# ChairControlMini.net
KiCad netlist of a schematic drawn in EAGLE
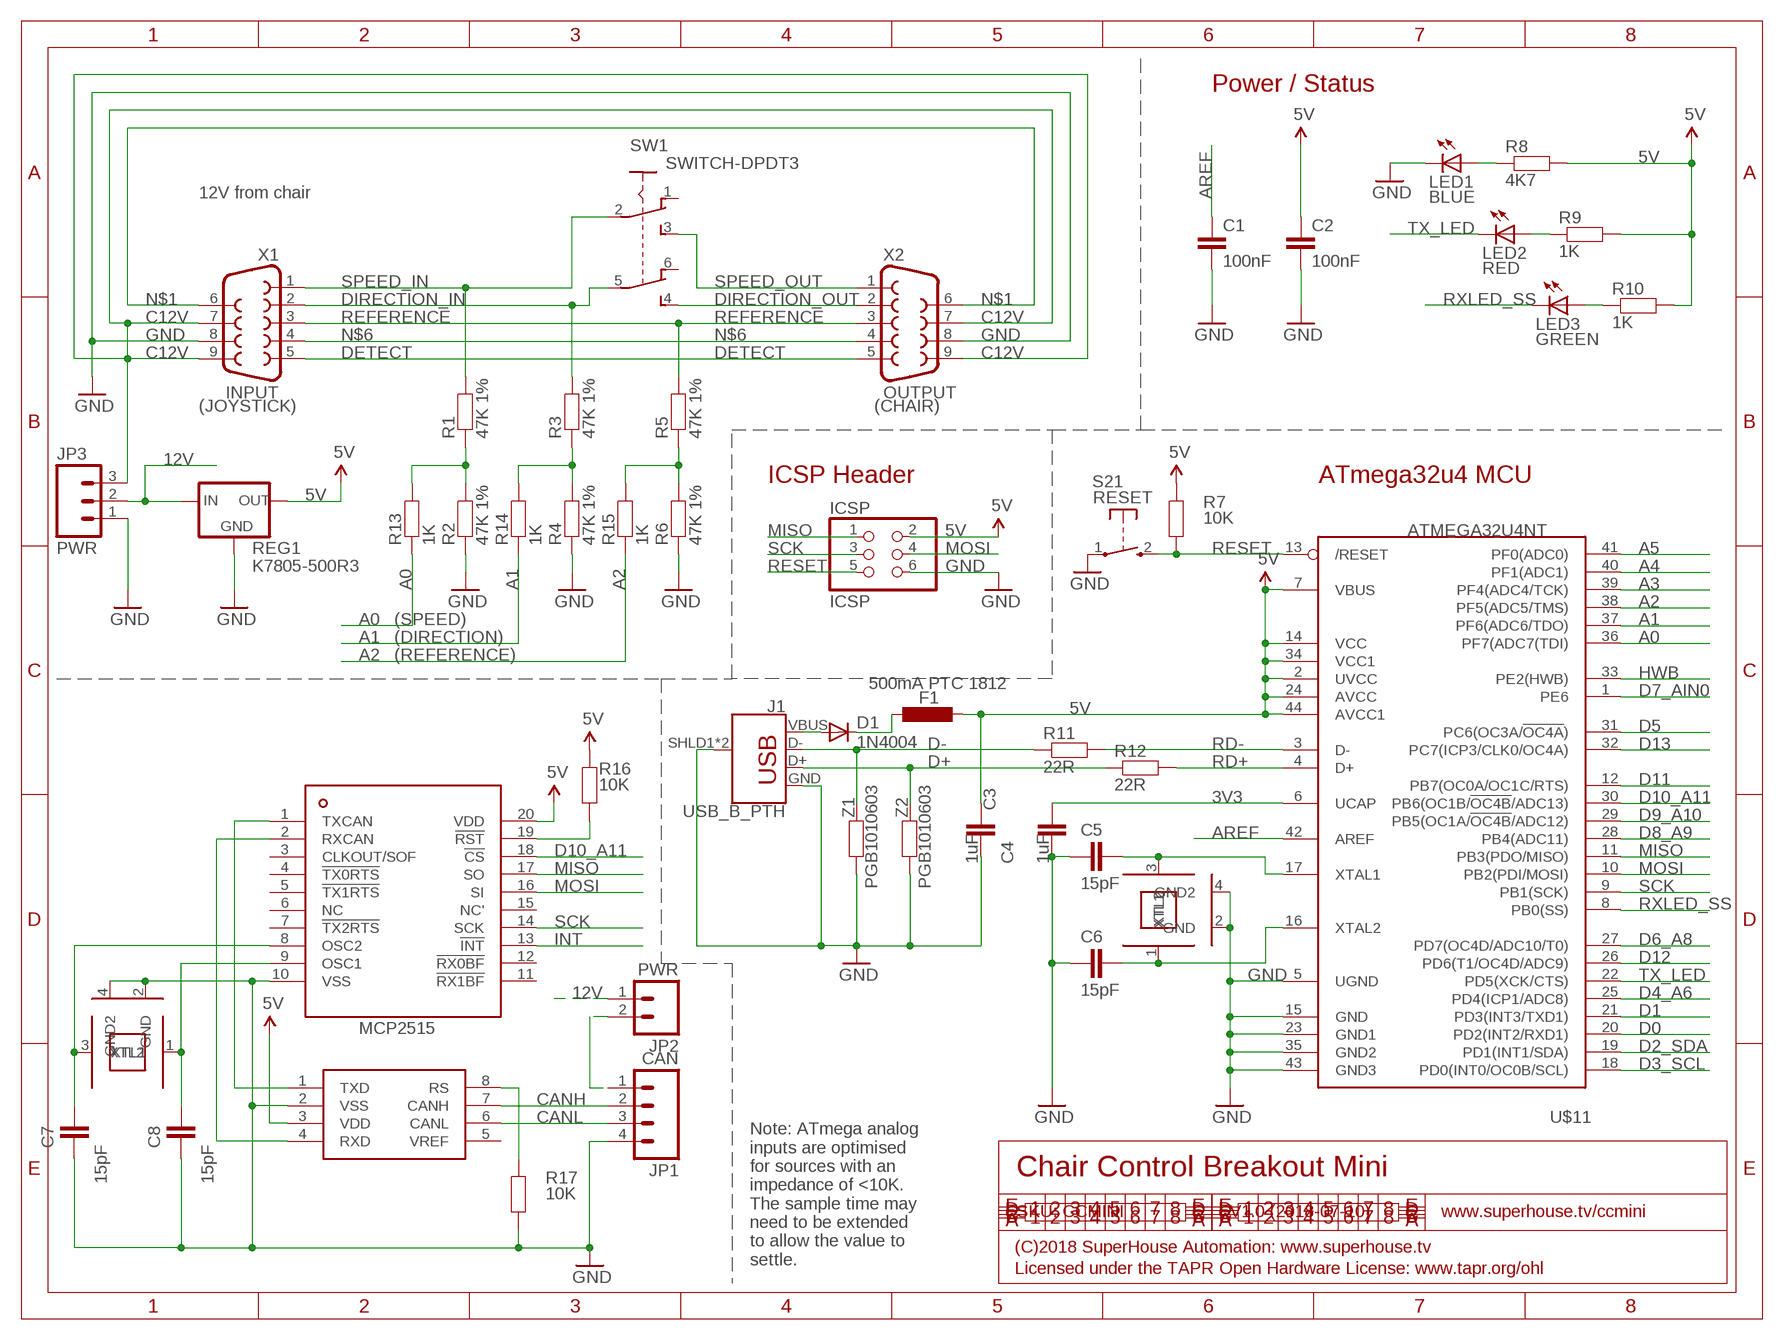
[diagram p0: schematic, sheet 1]

(export (version "E")
  (design (tool "Eeschema 10.0.6"))
  (components
    (comp (ref "C1")
      (value "100nF")
      (footprint "eagle-import:0603")
      (libsource (lib "eagle-import") (part "CAP0603"))
    )
    (comp (ref "C2")
      (value "100nF")
      (footprint "eagle-import:0603")
      (libsource (lib "eagle-import") (part "CAP0603"))
    )
    (comp (ref "C3")
      (value "1uF")
      (footprint "eagle-import:0603")
      (libsource (lib "eagle-import") (part "CAP0603"))
    )
    (comp (ref "C4")
      (value "1uF")
      (footprint "eagle-import:0603")
      (libsource (lib "eagle-import") (part "CAP0603"))
    )
    (comp (ref "C5")
      (value "15pF")
      (footprint "eagle-import:0603")
      (libsource (lib "eagle-import") (part "CAP0603"))
    )
    (comp (ref "C6")
      (value "15pF")
      (footprint "eagle-import:0603")
      (libsource (lib "eagle-import") (part "CAP0603"))
    )
    (comp (ref "C7")
      (value "15pF")
      (footprint "eagle-import:0603")
      (libsource (lib "eagle-import") (part "CAP0603"))
    )
    (comp (ref "C8")
      (value "15pF")
      (footprint "eagle-import:0603")
      (libsource (lib "eagle-import") (part "CAP0603"))
    )
    (comp (ref "D1")
      (value "1N4004")
      (footprint "eagle-import:SMB-DIODE")
      (libsource (lib "eagle-import") (part "DIODESMB"))
    )
    (comp (ref "F1")
      (value "500mA PTC 1812")
      (footprint "eagle-import:L1812")
      (libsource (lib "eagle-import") (part "L-EUL1812"))
    )
    (comp (ref "ICSP")
      (value "ICSP")
      (footprint "eagle-import:2X03")
      (libsource (lib "eagle-import") (part "PINHD-2X3"))
    )
    (comp (ref "J1")
      (value "USB_B_PTH")
      (footprint "eagle-import:USB-B-PTH")
      (libsource (lib "eagle-import") (part "USB_B_PTH"))
    )
    (comp (ref "JP1")
      (value "CAN")
      (footprint "eagle-import:1X04")
      (libsource (lib "eagle-import") (part "M04PTH"))
    )
    (comp (ref "JP2")
      (value "PWR")
      (footprint "eagle-import:1X02")
      (libsource (lib "eagle-import") (part "M02PTH"))
    )
    (comp (ref "JP3")
      (value "PWR")
      (footprint "eagle-import:1X03")
      (libsource (lib "eagle-import") (part "M03PTH"))
    )
    (comp (ref "LED1")
      (value "BLUE")
      (footprint "eagle-import:LED-0603")
      (libsource (lib "eagle-import") (part "LED0603"))
    )
    (comp (ref "LED2")
      (value "RED")
      (footprint "eagle-import:LED-0603")
      (libsource (lib "eagle-import") (part "LED0603"))
    )
    (comp (ref "LED3")
      (value "GREEN")
      (footprint "eagle-import:LED-0603")
      (libsource (lib "eagle-import") (part "LED0603"))
    )
    (comp (ref "R1")
      (value "47K 1%")
      (footprint "eagle-import:0603")
      (libsource (lib "eagle-import") (part "RESISTOR0603"))
    )
    (comp (ref "R2")
      (value "47K 1%")
      (footprint "eagle-import:0603")
      (libsource (lib "eagle-import") (part "RESISTOR0603"))
    )
    (comp (ref "R3")
      (value "47K 1%")
      (footprint "eagle-import:0603")
      (libsource (lib "eagle-import") (part "RESISTOR0603"))
    )
    (comp (ref "R4")
      (value "47K 1%")
      (footprint "eagle-import:0603")
      (libsource (lib "eagle-import") (part "RESISTOR0603"))
    )
    (comp (ref "R5")
      (value "47K 1%")
      (footprint "eagle-import:0603")
      (libsource (lib "eagle-import") (part "RESISTOR0603"))
    )
    (comp (ref "R6")
      (value "47K 1%")
      (footprint "eagle-import:0603")
      (libsource (lib "eagle-import") (part "RESISTOR0603"))
    )
    (comp (ref "R7")
      (value "10K")
      (footprint "eagle-import:0603")
      (libsource (lib "eagle-import") (part "freetronics-master-v1.1_RESISTOR0603"))
    )
    (comp (ref "R8")
      (value "4K7")
      (footprint "eagle-import:0603")
      (libsource (lib "eagle-import") (part "RESISTOR0603"))
    )
    (comp (ref "R9")
      (value "1K")
      (footprint "eagle-import:0603")
      (libsource (lib "eagle-import") (part "RESISTOR0603"))
    )
    (comp (ref "R10")
      (value "1K")
      (footprint "eagle-import:0603")
      (libsource (lib "eagle-import") (part "RESISTOR0603"))
    )
    (comp (ref "R11")
      (value "22R")
      (footprint "eagle-import:0603")
      (libsource (lib "eagle-import") (part "RESISTOR0603"))
    )
    (comp (ref "R12")
      (value "22R")
      (footprint "eagle-import:0603")
      (libsource (lib "eagle-import") (part "RESISTOR0603"))
    )
    (comp (ref "R13")
      (value "1K")
      (footprint "eagle-import:0603")
      (libsource (lib "eagle-import") (part "RESISTOR0603"))
    )
    (comp (ref "R14")
      (value "1K")
      (footprint "eagle-import:0603")
      (libsource (lib "eagle-import") (part "RESISTOR0603"))
    )
    (comp (ref "R15")
      (value "1K")
      (footprint "eagle-import:0603")
      (libsource (lib "eagle-import") (part "RESISTOR0603"))
    )
    (comp (ref "R16")
      (value "10K")
      (footprint "eagle-import:0603")
      (libsource (lib "eagle-import") (part "freetronics-master-v1.1_RESISTOR0603"))
    )
    (comp (ref "R17")
      (value "10K")
      (footprint "eagle-import:0603")
      (libsource (lib "eagle-import") (part "freetronics-master-v1.1_RESISTOR0603"))
    )
    (comp (ref "REG1")
      (value "K7805-500R3")
      (footprint "eagle-import:K78XX-500R3")
      (libsource (lib "eagle-import") (part "K78XX-500R3"))
    )
    (comp (ref "S21")
      (value "RESET")
      (footprint "eagle-import:TACTILE_SWITCH_SMD_2PIN_TINY")
      (libsource (lib "eagle-import") (part "TAC_SWITCH_2PINSMT"))
    )
    (comp (ref "SW1")
      (value "SWITCH-DPDT3")
      (footprint "eagle-import:7201SD9AV2BE")
      (libsource (lib "eagle-import") (part "SWITCH-DPDT3"))
    )
    (comp (ref "U$4")
      (value "MCP2515")
      (footprint "eagle-import:TSSOP20")
      (libsource (lib "eagle-import") (part "MCP2515"))
    )
    (comp (ref "U$11")
      (value "ATMEGA32U4NT")
      (footprint "eagle-import:TQFP44")
      (libsource (lib "eagle-import") (part "ATMEGA32U4NT"))
    )
    (comp (ref "U1")
      (value "MCP2551")
      (footprint "eagle-import:SO08")
      (libsource (lib "eagle-import") (part "MCP2551"))
    )
    (comp (ref "X1")
      (value "INPUT")
      (footprint "eagle-import:DB9_MALE")
      (libsource (lib "eagle-import") (part "DB9MALE"))
    )
    (comp (ref "X2")
      (value "OUTPUT")
      (footprint "eagle-import:DB9")
      (libsource (lib "eagle-import") (part "DB9FEMALE"))
    )
    (comp (ref "XTL1")
      (value "16MHz")
      (footprint "eagle-import:CRYSTAL-SMD-3X2")
      (libsource (lib "eagle-import") (part "CRYSTAL-GND3X2"))
    )
    (comp (ref "XTL2")
      (value "8MHz")
      (footprint "eagle-import:CRYSTAL-SMD-3X2")
      (libsource (lib "eagle-import") (part "CRYSTAL-GND3X2"))
    )
    (comp (ref "Z1")
      (value "PGB1010603")
      (footprint "eagle-import:0603")
      (libsource (lib "eagle-import") (part "freetronics-master-v1.1_RESISTOR0603"))
    )
    (comp (ref "Z2")
      (value "PGB1010603")
      (footprint "eagle-import:0603")
      (libsource (lib "eagle-import") (part "freetronics-master-v1.1_RESISTOR0603"))
    )
  )
  (nets
    (net (code "1") (name "/3V3") (class "Default")
      (node (ref "C4") (pin "2") (pinfunction "2_2") (pintype "passive"))
      (node (ref "U$11") (pin "6") (pinfunction "UCAP_6") (pintype "bidirectional"))
    )
    (net (code "2") (name "/12V") (class "Default")
      (node (ref "JP2") (pin "1") (pinfunction "1_1") (pintype "passive"))
      (node (ref "JP3") (pin "2") (pinfunction "2_2") (pintype "passive"))
      (node (ref "REG1") (pin "1") (pinfunction "IN_1") (pintype "input"))
    )
    (net (code "3") (name "/A0") (class "Default")
      (node (ref "R13") (pin "1") (pinfunction "1_1") (pintype "passive"))
      (node (ref "U$11") (pin "36") (pinfunction "PF7(ADC7(TDI)_36") (pintype "bidirectional"))
    )
    (net (code "4") (name "/A1") (class "Default")
      (node (ref "R14") (pin "1") (pinfunction "1_1") (pintype "passive"))
      (node (ref "U$11") (pin "37") (pinfunction "PF6(ADC6/TDO)_37") (pintype "bidirectional"))
    )
    (net (code "5") (name "/A2") (class "Default")
      (node (ref "R15") (pin "1") (pinfunction "1_1") (pintype "passive"))
      (node (ref "U$11") (pin "38") (pinfunction "PF5(ADC5/TMS)_38") (pintype "bidirectional"))
    )
    (net (code "6") (name "/A3") (class "Default")
      (node (ref "U$11") (pin "39") (pinfunction "PF4(ADC4/TCK)_39") (pintype "bidirectional"))
    )
    (net (code "7") (name "/A4") (class "Default")
      (node (ref "U$11") (pin "40") (pinfunction "PF1(ADC1)_40") (pintype "bidirectional"))
    )
    (net (code "8") (name "/A5") (class "Default")
      (node (ref "U$11") (pin "41") (pinfunction "PF0(ADC0)_41") (pintype "bidirectional"))
    )
    (net (code "9") (name "/AREF") (class "Default")
      (node (ref "C1") (pin "1") (pinfunction "1_1") (pintype "passive"))
      (node (ref "U$11") (pin "42") (pinfunction "AREF_42") (pintype "bidirectional"))
    )
    (net (code "10") (name "/C12V") (class "Default")
      (node (ref "JP3") (pin "3") (pinfunction "3_3") (pintype "passive"))
      (node (ref "X1") (pin "7") (pinfunction "7_7") (pintype "passive"))
      (node (ref "X1") (pin "9") (pinfunction "9_9") (pintype "passive"))
      (node (ref "X2") (pin "7") (pinfunction "7_7") (pintype "passive"))
      (node (ref "X2") (pin "9") (pinfunction "9_9") (pintype "passive"))
    )
    (net (code "11") (name "/CANH") (class "Default")
      (node (ref "JP1") (pin "2") (pinfunction "2_2") (pintype "passive"))
      (node (ref "U1") (pin "7") (pinfunction "CANH_7") (pintype "bidirectional"))
    )
    (net (code "12") (name "/CANL") (class "Default")
      (node (ref "JP1") (pin "3") (pinfunction "3_3") (pintype "passive"))
      (node (ref "U1") (pin "6") (pinfunction "CANL_6") (pintype "bidirectional"))
    )
    (net (code "13") (name "/D+") (class "Default")
      (node (ref "J1") (pin "D+") (pinfunction "D+_D+") (pintype "bidirectional"))
      (node (ref "R12") (pin "1") (pinfunction "1_1") (pintype "passive"))
      (node (ref "Z2") (pin "2") (pinfunction "2_2") (pintype "passive"))
    )
    (net (code "14") (name "/D-") (class "Default")
      (node (ref "J1") (pin "D-") (pinfunction "D-_D-") (pintype "bidirectional"))
      (node (ref "R11") (pin "1") (pinfunction "1_1") (pintype "passive"))
      (node (ref "Z1") (pin "2") (pinfunction "2_2") (pintype "passive"))
    )
    (net (code "15") (name "/D0") (class "Default")
      (node (ref "U$11") (pin "20") (pinfunction "PD2(INT2/RXD1)_20") (pintype "bidirectional"))
    )
    (net (code "16") (name "/D1") (class "Default")
      (node (ref "U$11") (pin "21") (pinfunction "PD3(INT3/TXD1)_21") (pintype "bidirectional"))
    )
    (net (code "17") (name "/D2_SDA") (class "Default")
      (node (ref "U$11") (pin "19") (pinfunction "PD1(INT1/SDA)_19") (pintype "bidirectional"))
    )
    (net (code "18") (name "/D3_SCL") (class "Default")
      (node (ref "U$11") (pin "18") (pinfunction "PD0(INT0/OC0B/SCL)_18") (pintype "bidirectional"))
    )
    (net (code "19") (name "/D4_A6") (class "Default")
      (node (ref "U$11") (pin "25") (pinfunction "PD4(ICP1/ADC8)_25") (pintype "bidirectional"))
    )
    (net (code "20") (name "/D5") (class "Default")
      (node (ref "U$11") (pin "31") (pinfunction "PC6(OC3A/~{OC4A})_31") (pintype "bidirectional"))
    )
    (net (code "21") (name "/D6_A8") (class "Default")
      (node (ref "U$11") (pin "27") (pinfunction "PD7(OC4D/ADC10/T0)_27") (pintype "bidirectional"))
    )
    (net (code "22") (name "/D7_AIN0") (class "Default")
      (node (ref "U$11") (pin "1") (pinfunction "PE6_1") (pintype "bidirectional"))
    )
    (net (code "23") (name "/D8_A9") (class "Default")
      (node (ref "U$11") (pin "28") (pinfunction "PB4(ADC11)_28") (pintype "bidirectional"))
    )
    (net (code "24") (name "/D9_A10") (class "Default")
      (node (ref "U$11") (pin "29") (pinfunction "PB5(OC1A/~{OC4B}/ADC12)_29") (pintype "bidirectional"))
    )
    (net (code "25") (name "/D10_A11") (class "Default")
      (node (ref "U$11") (pin "30") (pinfunction "PB6(OC1B/~{OC4B}/ADC13)_30") (pintype "bidirectional"))
      (node (ref "U$4") (pin "18") (pinfunction "~{CS}_18") (pintype "bidirectional"))
    )
    (net (code "26") (name "/D11") (class "Default")
      (node (ref "U$11") (pin "12") (pinfunction "PB7(OC0A/OC1C/RTS)_12") (pintype "bidirectional"))
    )
    (net (code "27") (name "/D12") (class "Default")
      (node (ref "U$11") (pin "26") (pinfunction "PD6(T1/OC4D/ADC9)_26") (pintype "bidirectional"))
    )
    (net (code "28") (name "/D13") (class "Default")
      (node (ref "U$11") (pin "32") (pinfunction "PC7(ICP3/CLK0/OC4A)_32") (pintype "bidirectional"))
    )
    (net (code "29") (name "/DETECT") (class "Default")
      (node (ref "X1") (pin "5") (pinfunction "5_5") (pintype "passive"))
      (node (ref "X2") (pin "5") (pinfunction "5_5") (pintype "passive"))
    )
    (net (code "30") (name "/DIRECTION_IN") (class "Default")
      (node (ref "R3") (pin "2") (pinfunction "2_2") (pintype "passive"))
      (node (ref "SW1") (pin "5") (pinfunction "5_5") (pintype "passive"))
      (node (ref "X1") (pin "2") (pinfunction "2_2") (pintype "passive"))
    )
    (net (code "31") (name "/DIRECTION_OUT") (class "Default")
      (node (ref "SW1") (pin "4") (pinfunction "4_4") (pintype "passive"))
      (node (ref "X2") (pin "2") (pinfunction "2_2") (pintype "passive"))
    )
    (net (code "32") (name "/HWB") (class "Default")
      (node (ref "U$11") (pin "33") (pinfunction "PE2(HWB)_33") (pintype "bidirectional"))
    )
    (net (code "33") (name "/INT") (class "Default")
      (node (ref "U$4") (pin "13") (pinfunction "~{INT}_13") (pintype "bidirectional"))
    )
    (net (code "34") (name "/MISO") (class "Default")
      (node (ref "ICSP") (pin "1") (pinfunction "1_1") (pintype "passive"))
      (node (ref "U$11") (pin "11") (pinfunction "PB3(PDO/MISO)_11") (pintype "bidirectional"))
      (node (ref "U$4") (pin "17") (pinfunction "SO_17") (pintype "bidirectional"))
    )
    (net (code "35") (name "/MOSI") (class "Default")
      (node (ref "ICSP") (pin "4") (pinfunction "4_4") (pintype "passive"))
      (node (ref "U$11") (pin "10") (pinfunction "PB2(PDI/MOSI)_10") (pintype "bidirectional"))
      (node (ref "U$4") (pin "16") (pinfunction "SI_16") (pintype "bidirectional"))
    )
    (net (code "36") (name "/N$1") (class "Default")
      (node (ref "X1") (pin "6") (pinfunction "6_6") (pintype "passive"))
      (node (ref "X2") (pin "6") (pinfunction "6_6") (pintype "passive"))
    )
    (net (code "37") (name "/N$6") (class "Default")
      (node (ref "X1") (pin "4") (pinfunction "4_4") (pintype "passive"))
      (node (ref "X2") (pin "4") (pinfunction "4_4") (pintype "passive"))
    )
    (net (code "38") (name "/RD+") (class "Default")
      (node (ref "R12") (pin "2") (pinfunction "2_2") (pintype "passive"))
      (node (ref "U$11") (pin "4") (pinfunction "D+_4") (pintype "bidirectional"))
    )
    (net (code "39") (name "/RD-") (class "Default")
      (node (ref "R11") (pin "2") (pinfunction "2_2") (pintype "passive"))
      (node (ref "U$11") (pin "3") (pinfunction "D-_3") (pintype "bidirectional"))
    )
    (net (code "40") (name "/REFERENCE") (class "Default")
      (node (ref "R5") (pin "2") (pinfunction "2_2") (pintype "passive"))
      (node (ref "X1") (pin "3") (pinfunction "3_3") (pintype "passive"))
      (node (ref "X2") (pin "3") (pinfunction "3_3") (pintype "passive"))
    )
    (net (code "41") (name "/RESET") (class "Default")
      (node (ref "ICSP") (pin "5") (pinfunction "5_5") (pintype "passive"))
      (node (ref "R7") (pin "1") (pinfunction "1_1") (pintype "passive"))
      (node (ref "S21") (pin "2") (pinfunction "S_2") (pintype "passive"))
      (node (ref "U$11") (pin "13") (pinfunction "/RESET_13") (pintype "bidirectional"))
    )
    (net (code "42") (name "/RXLED_SS") (class "Default")
      (node (ref "LED3") (pin "C") (pinfunction "C_C") (pintype "passive"))
      (node (ref "U$11") (pin "8") (pinfunction "PB0(SS)_8") (pintype "bidirectional"))
    )
    (net (code "43") (name "/SCK") (class "Default")
      (node (ref "ICSP") (pin "3") (pinfunction "3_3") (pintype "passive"))
      (node (ref "U$11") (pin "9") (pinfunction "PB1(SCK)_9") (pintype "bidirectional"))
      (node (ref "U$4") (pin "14") (pinfunction "SCK_14") (pintype "bidirectional"))
    )
    (net (code "44") (name "/SPEED_IN") (class "Default")
      (node (ref "R1") (pin "2") (pinfunction "2_2") (pintype "passive"))
      (node (ref "SW1") (pin "2") (pinfunction "2_2") (pintype "passive"))
      (node (ref "X1") (pin "1") (pinfunction "1_1") (pintype "passive"))
    )
    (net (code "45") (name "/SPEED_OUT") (class "Default")
      (node (ref "SW1") (pin "3") (pinfunction "3_3") (pintype "passive"))
      (node (ref "X2") (pin "1") (pinfunction "1_1") (pintype "passive"))
    )
    (net (code "46") (name "/TX_LED") (class "Default")
      (node (ref "LED2") (pin "C") (pinfunction "C_C") (pintype "passive"))
      (node (ref "U$11") (pin "22") (pinfunction "PD5(XCK/CTS)_22") (pintype "bidirectional"))
    )
    (net (code "47") (name "5V") (class "Default")
      (node (ref "C2") (pin "1") (pinfunction "1_1") (pintype "passive"))
      (node (ref "C3") (pin "1") (pinfunction "1_1") (pintype "passive"))
      (node (ref "F1") (pin "2") (pinfunction "2_2") (pintype "passive"))
      (node (ref "ICSP") (pin "2") (pinfunction "2_2") (pintype "passive"))
      (node (ref "R10") (pin "2") (pinfunction "2_2") (pintype "passive"))
      (node (ref "R16") (pin "2") (pinfunction "2_2") (pintype "passive"))
      (node (ref "R7") (pin "2") (pinfunction "2_2") (pintype "passive"))
      (node (ref "R8") (pin "2") (pinfunction "2_2") (pintype "passive"))
      (node (ref "R9") (pin "2") (pinfunction "2_2") (pintype "passive"))
      (node (ref "REG1") (pin "3") (pinfunction "OUT_3") (pintype "output"))
      (node (ref "U$11") (pin "14") (pinfunction "VCC_14") (pintype "bidirectional"))
      (node (ref "U$11") (pin "2") (pinfunction "UVCC_2") (pintype "bidirectional"))
      (node (ref "U$11") (pin "24") (pinfunction "AVCC_24") (pintype "bidirectional"))
      (node (ref "U$11") (pin "34") (pinfunction "VCC1_34") (pintype "bidirectional"))
      (node (ref "U$11") (pin "44") (pinfunction "AVCC1_44") (pintype "bidirectional"))
      (node (ref "U$11") (pin "7") (pinfunction "VBUS_7") (pintype "bidirectional"))
      (node (ref "U$4") (pin "20") (pinfunction "VDD_20") (pintype "bidirectional"))
      (node (ref "U1") (pin "3") (pinfunction "VDD_3") (pintype "bidirectional"))
    )
    (net (code "48") (name "GND") (class "Default")
      (node (ref "C1") (pin "2") (pinfunction "2_2") (pintype "passive"))
      (node (ref "C2") (pin "2") (pinfunction "2_2") (pintype "passive"))
      (node (ref "C3") (pin "2") (pinfunction "2_2") (pintype "passive"))
      (node (ref "C4") (pin "1") (pinfunction "1_1") (pintype "passive"))
      (node (ref "C5") (pin "1") (pinfunction "1_1") (pintype "passive"))
      (node (ref "C6") (pin "1") (pinfunction "1_1") (pintype "passive"))
      (node (ref "C7") (pin "1") (pinfunction "1_1") (pintype "passive"))
      (node (ref "C8") (pin "1") (pinfunction "1_1") (pintype "passive"))
      (node (ref "ICSP") (pin "6") (pinfunction "6_6") (pintype "passive"))
      (node (ref "J1") (pin "GND") (pinfunction "GND_GND") (pintype "power_in"))
      (node (ref "J1") (pin "SHLD1") (pinfunction "SHIELD_SHLD1") (pintype "bidirectional"))
      (node (ref "J1") (pin "SHLD2") (pinfunction "SHIELD_SHLD2") (pintype "bidirectional"))
      (node (ref "JP1") (pin "4") (pinfunction "4_4") (pintype "passive"))
      (node (ref "JP3") (pin "1") (pinfunction "1_1") (pintype "passive"))
      (node (ref "LED1") (pin "C") (pinfunction "C_C") (pintype "passive"))
      (node (ref "R17") (pin "1") (pinfunction "1_1") (pintype "passive"))
      (node (ref "R2") (pin "1") (pinfunction "1_1") (pintype "passive"))
      (node (ref "R4") (pin "1") (pinfunction "1_1") (pintype "passive"))
      (node (ref "R6") (pin "1") (pinfunction "1_1") (pintype "passive"))
      (node (ref "REG1") (pin "2") (pinfunction "GND_2") (pintype "input"))
      (node (ref "S21") (pin "1") (pinfunction "P_1") (pintype "passive"))
      (node (ref "U$11") (pin "15") (pinfunction "GND_15") (pintype "bidirectional"))
      (node (ref "U$11") (pin "23") (pinfunction "GND1_23") (pintype "bidirectional"))
      (node (ref "U$11") (pin "35") (pinfunction "GND2_35") (pintype "bidirectional"))
      (node (ref "U$11") (pin "43") (pinfunction "GND3_43") (pintype "bidirectional"))
      (node (ref "U$11") (pin "5") (pinfunction "UGND_5") (pintype "bidirectional"))
      (node (ref "U$4") (pin "10") (pinfunction "VSS_10") (pintype "bidirectional"))
      (node (ref "U1") (pin "2") (pinfunction "VSS_2") (pintype "bidirectional"))
      (node (ref "X1") (pin "8") (pinfunction "8_8") (pintype "passive"))
      (node (ref "X2") (pin "8") (pinfunction "8_8") (pintype "passive"))
      (node (ref "XTL1") (pin "2") (pinfunction "GND_2") (pintype "bidirectional"))
      (node (ref "XTL1") (pin "4") (pinfunction "GND2_4") (pintype "bidirectional"))
      (node (ref "XTL2") (pin "2") (pinfunction "GND_2") (pintype "bidirectional"))
      (node (ref "XTL2") (pin "4") (pinfunction "GND2_4") (pintype "bidirectional"))
      (node (ref "Z1") (pin "1") (pinfunction "1_1") (pintype "passive"))
      (node (ref "Z2") (pin "1") (pinfunction "1_1") (pintype "passive"))
    )
    (net (code "49") (name "Net-(D1-PadA)") (class "Default")
      (node (ref "D1") (pin "A") (pinfunction "A_A") (pintype "passive"))
      (node (ref "J1") (pin "VBUS") (pinfunction "VBUS_VBUS") (pintype "power_in"))
    )
    (net (code "50") (name "Net-(D1-PadC)") (class "Default")
      (node (ref "D1") (pin "C") (pinfunction "C_C") (pintype "passive"))
      (node (ref "F1") (pin "1") (pinfunction "1_1") (pintype "passive"))
    )
    (net (code "51") (name "Net-(JP1-Pad1)") (class "Default")
      (node (ref "JP1") (pin "1") (pinfunction "1_1") (pintype "passive"))
      (node (ref "JP2") (pin "2") (pinfunction "2_2") (pintype "passive"))
    )
    (net (code "52") (name "Net-(LED1-PadA)") (class "Default")
      (node (ref "LED1") (pin "A") (pinfunction "A_A") (pintype "passive"))
      (node (ref "R8") (pin "1") (pinfunction "1_1") (pintype "passive"))
    )
    (net (code "53") (name "Net-(LED2-PadA)") (class "Default")
      (node (ref "LED2") (pin "A") (pinfunction "A_A") (pintype "passive"))
      (node (ref "R9") (pin "1") (pinfunction "1_1") (pintype "passive"))
    )
    (net (code "54") (name "Net-(LED3-PadA)") (class "Default")
      (node (ref "LED3") (pin "A") (pinfunction "A_A") (pintype "passive"))
      (node (ref "R10") (pin "1") (pinfunction "1_1") (pintype "passive"))
    )
    (net (code "55") (name "Net-(R1-Pad1)") (class "Default")
      (node (ref "R1") (pin "1") (pinfunction "1_1") (pintype "passive"))
      (node (ref "R13") (pin "2") (pinfunction "2_2") (pintype "passive"))
      (node (ref "R2") (pin "2") (pinfunction "2_2") (pintype "passive"))
    )
    (net (code "56") (name "Net-(R14-Pad2)") (class "Default")
      (node (ref "R14") (pin "2") (pinfunction "2_2") (pintype "passive"))
      (node (ref "R3") (pin "1") (pinfunction "1_1") (pintype "passive"))
      (node (ref "R4") (pin "2") (pinfunction "2_2") (pintype "passive"))
    )
    (net (code "57") (name "Net-(R15-Pad2)") (class "Default")
      (node (ref "R15") (pin "2") (pinfunction "2_2") (pintype "passive"))
      (node (ref "R5") (pin "1") (pinfunction "1_1") (pintype "passive"))
      (node (ref "R6") (pin "2") (pinfunction "2_2") (pintype "passive"))
    )
    (net (code "58") (name "Net-(U$4-OSC1)") (class "Default")
      (node (ref "C8") (pin "2") (pinfunction "2_2") (pintype "passive"))
      (node (ref "U$4") (pin "9") (pinfunction "OSC1_9") (pintype "bidirectional"))
      (node (ref "XTL2") (pin "1") (pinfunction "XTL1_1") (pintype "bidirectional"))
    )
    (net (code "59") (name "Net-(U$4-OSC2)") (class "Default")
      (node (ref "C7") (pin "2") (pinfunction "2_2") (pintype "passive"))
      (node (ref "U$4") (pin "8") (pinfunction "OSC2_8") (pintype "bidirectional"))
      (node (ref "XTL2") (pin "3") (pinfunction "XTL2_3") (pintype "bidirectional"))
    )
    (net (code "60") (name "Net-(U$4-RXCAN)") (class "Default")
      (node (ref "U$4") (pin "2") (pinfunction "RXCAN_2") (pintype "bidirectional"))
      (node (ref "U1") (pin "4") (pinfunction "RXD_4") (pintype "bidirectional"))
    )
    (net (code "61") (name "Net-(U$4-TXCAN)") (class "Default")
      (node (ref "U$4") (pin "1") (pinfunction "TXCAN_1") (pintype "bidirectional"))
      (node (ref "U1") (pin "1") (pinfunction "TXD_1") (pintype "bidirectional"))
    )
    (net (code "62") (name "Net-(U$4-~{RST})") (class "Default")
      (node (ref "R16") (pin "1") (pinfunction "1_1") (pintype "passive"))
      (node (ref "U$4") (pin "19") (pinfunction "~{RST}_19") (pintype "bidirectional"))
    )
    (net (code "63") (name "Net-(U$11-XTAL1)") (class "Default")
      (node (ref "C5") (pin "2") (pinfunction "2_2") (pintype "passive"))
      (node (ref "U$11") (pin "17") (pinfunction "XTAL1_17") (pintype "bidirectional"))
      (node (ref "XTL1") (pin "3") (pinfunction "XTL2_3") (pintype "bidirectional"))
    )
    (net (code "64") (name "Net-(U$11-XTAL2)") (class "Default")
      (node (ref "C6") (pin "2") (pinfunction "2_2") (pintype "passive"))
      (node (ref "U$11") (pin "16") (pinfunction "XTAL2_16") (pintype "bidirectional"))
      (node (ref "XTL1") (pin "1") (pinfunction "XTL1_1") (pintype "bidirectional"))
    )
    (net (code "65") (name "Net-(U1-RS)") (class "Default")
      (node (ref "R17") (pin "2") (pinfunction "2_2") (pintype "passive"))
      (node (ref "U1") (pin "8") (pinfunction "RS_8") (pintype "bidirectional"))
    )
    (net (code "66") (name "unconnected-(SW1-Pad1)") (class "Default")
      (node (ref "SW1") (pin "1") (pinfunction "1_1") (pintype "passive"))
    )
    (net (code "67") (name "unconnected-(SW1-Pad6)") (class "Default")
      (node (ref "SW1") (pin "6") (pinfunction "6_6") (pintype "passive"))
    )
    (net (code "68") (name "unconnected-(U$4-CLKOUT{slash}SOF-Pad3)") (class "Default")
      (node (ref "U$4") (pin "3") (pinfunction "CLKOUT/SOF_3") (pintype "bidirectional"))
    )
    (net (code "69") (name "unconnected-(U$4-NC'-Pad15)") (class "Default")
      (node (ref "U$4") (pin "15") (pinfunction "NC'_15") (pintype "bidirectional"))
    )
    (net (code "70") (name "unconnected-(U$4-NC-Pad6)") (class "Default")
      (node (ref "U$4") (pin "6") (pinfunction "NC_6") (pintype "bidirectional"))
    )
    (net (code "71") (name "unconnected-(U$4-~{RX0BF}-Pad12)") (class "Default")
      (node (ref "U$4") (pin "12") (pinfunction "~{RX0BF}_12") (pintype "bidirectional"))
    )
    (net (code "72") (name "unconnected-(U$4-~{RX1BF}-Pad11)") (class "Default")
      (node (ref "U$4") (pin "11") (pinfunction "~{RX1BF}_11") (pintype "bidirectional"))
    )
    (net (code "73") (name "unconnected-(U$4-~{TX0RTS}-Pad4)") (class "Default")
      (node (ref "U$4") (pin "4") (pinfunction "~{TX0RTS}_4") (pintype "bidirectional"))
    )
    (net (code "74") (name "unconnected-(U$4-~{TX1RTS}-Pad5)") (class "Default")
      (node (ref "U$4") (pin "5") (pinfunction "~{TX1RTS}_5") (pintype "bidirectional"))
    )
    (net (code "75") (name "unconnected-(U$4-~{TX2RTS}-Pad7)") (class "Default")
      (node (ref "U$4") (pin "7") (pinfunction "~{TX2RTS}_7") (pintype "bidirectional"))
    )
    (net (code "76") (name "unconnected-(U1-VREF-Pad5)") (class "Default")
      (node (ref "U1") (pin "5") (pinfunction "VREF_5") (pintype "bidirectional"))
    )
  )
)
